# 7_seg_display.net
KiCad netlist of a schematic drawn in Altium Designer
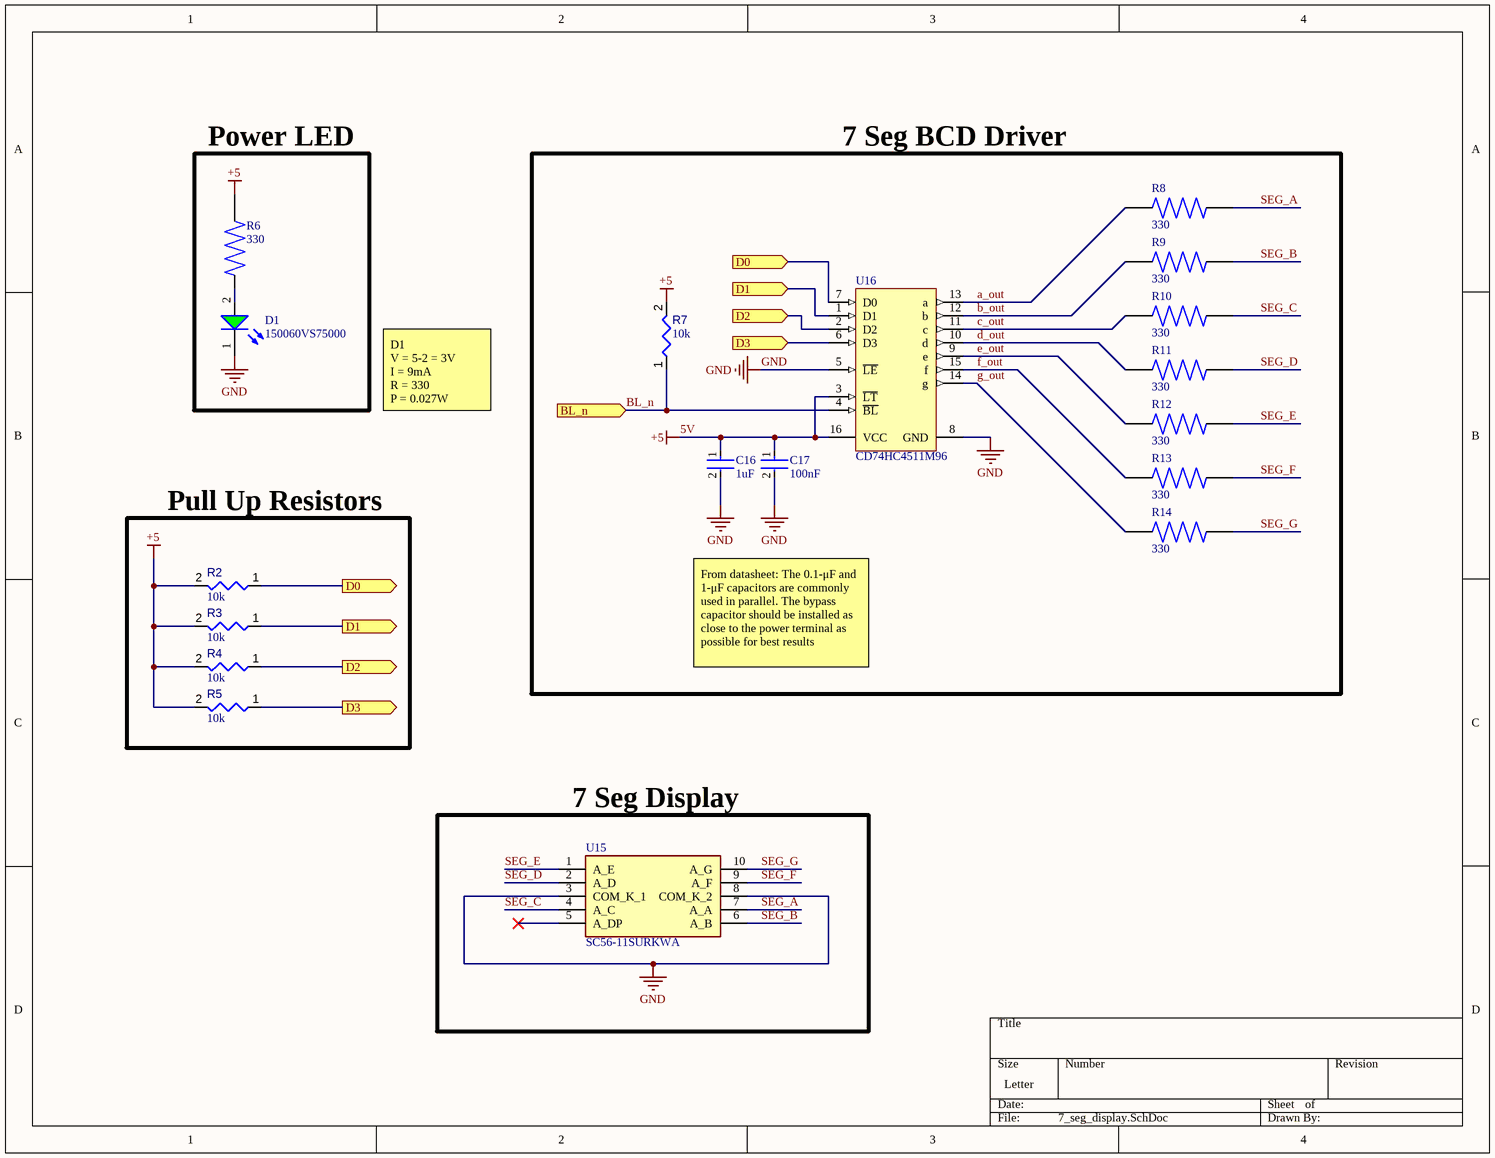
[diagram p0: 7_seg_display.SchDoc]

(export (version "E")
  (design (tool "Eeschema 10.0.6"))
  (components
    (comp (ref "C16")
      (value "1uF")
      (footprint "FP-CGA3E-0_3-0_1-IPC_A")
      (description "Cap Ceramic 1uF 16V X7R 10% Pad SMD 0603 +125°C Automotive T/R")
      (fields (field (name "TOLERANCE") "10%"))
      (libsource (lib "Altium Content Vault") (part "b4654b650e69147ec39a6b967a45e02"))
    )
    (comp (ref "C17")
      (value "100nF")
      (footprint "FP-CL10-IPC_A")
      (description "Cap Ceramic 100nF 16V X7R ±10% Pad SMD 0603 +125°C T/R")
      (fields (field (name "TOLERANCE") "10%"))
      (libsource (lib "Altium Content Vault") (part "b4654b650e69147ec39a6b967a45e02"))
    )
    (comp (ref "D1")
      (value "150060VS75000")
      (footprint "WL-SMCW_0603_150060xx75000")
      (description "WURTH ELEKTRONIK - 150060VS75000 - LED, Green, SMD, 0603, 30 mA, 2 V, 570 nm")
      (libsource (lib "Altium Content Vault") (part "LED_Green_2A-1K"))
    )
    (comp (ref "R2")
      (value "10k")
      (footprint "RESC1608X55X25ML10T15")
      (description "Chip Resistor, 10 KOhm, +/- 1%, 01 W, -55 to 155 degC, 0603 (1608 Metric)")
      (fields (field (name "POWER") "100mW") (field (name "TOLERANCE") "1%"))
      (libsource (lib "Lin Fu") (part "RES-2"))
    )
    (comp (ref "R3")
      (value "10k")
      (footprint "RESC1608X55X25ML10T15")
      (description "Chip Resistor, 10 KOhm, +/- 1%, 01 W, -55 to 155 degC, 0603 (1608 Metric)")
      (fields (field (name "POWER") "100mW") (field (name "TOLERANCE") "1%"))
      (libsource (lib "Lin Fu") (part "RES-2"))
    )
    (comp (ref "R4")
      (value "10k")
      (footprint "RESC1608X55X25ML10T15")
      (description "Chip Resistor, 10 KOhm, +/- 1%, 01 W, -55 to 155 degC, 0603 (1608 Metric)")
      (fields (field (name "POWER") "100mW") (field (name "TOLERANCE") "1%"))
      (libsource (lib "Lin Fu") (part "RES-2"))
    )
    (comp (ref "R5")
      (value "10k")
      (footprint "RESC1608X55X25ML10T15")
      (description "Chip Resistor, 10 KOhm, +/- 1%, 01 W, -55 to 155 degC, 0603 (1608 Metric)")
      (fields (field (name "POWER") "100mW") (field (name "TOLERANCE") "1%"))
      (libsource (lib "Lin Fu") (part "RES-2"))
    )
    (comp (ref "R6")
      (value "330")
      (footprint "RES_ERJ-PB3B3300V")
      (fields (field (name "MP") "ERJ-PB3B3300V") (field (name "MF") "Panasonic"))
      (libsource (lib "Lin Fu") (part "ERJ-PB3B3300V"))
    )
    (comp (ref "R7")
      (value "10k")
      (footprint "RESC1608X55X25ML10T15")
      (description "Chip Resistor, 10 KOhm, +/- 1%, 01 W, -55 to 155 degC, 0603 (1608 Metric)")
      (fields (field (name "POWER") "100mW") (field (name "TOLERANCE") "1%"))
      (libsource (lib "Lin Fu") (part "RES-2"))
    )
    (comp (ref "R8")
      (value "330")
      (footprint "RES_ERJ-PB3B3300V")
      (fields (field (name "MP") "ERJ-PB3B3300V") (field (name "MF") "Panasonic"))
      (libsource (lib "Lin Fu") (part "ERJ-PB3B3300V"))
    )
    (comp (ref "R9")
      (value "330")
      (footprint "RES_ERJ-PB3B3300V")
      (fields (field (name "MP") "ERJ-PB3B3300V") (field (name "MF") "Panasonic"))
      (libsource (lib "Lin Fu") (part "ERJ-PB3B3300V"))
    )
    (comp (ref "R10")
      (value "330")
      (footprint "RES_ERJ-PB3B3300V")
      (fields (field (name "MP") "ERJ-PB3B3300V") (field (name "MF") "Panasonic"))
      (libsource (lib "Lin Fu") (part "ERJ-PB3B3300V"))
    )
    (comp (ref "R11")
      (value "330")
      (footprint "RES_ERJ-PB3B3300V")
      (fields (field (name "MP") "ERJ-PB3B3300V") (field (name "MF") "Panasonic"))
      (libsource (lib "Lin Fu") (part "ERJ-PB3B3300V"))
    )
    (comp (ref "R12")
      (value "330")
      (footprint "RES_ERJ-PB3B3300V")
      (fields (field (name "MP") "ERJ-PB3B3300V") (field (name "MF") "Panasonic"))
      (libsource (lib "Lin Fu") (part "ERJ-PB3B3300V"))
    )
    (comp (ref "R13")
      (value "330")
      (footprint "RES_ERJ-PB3B3300V")
      (fields (field (name "MP") "ERJ-PB3B3300V") (field (name "MF") "Panasonic"))
      (libsource (lib "Lin Fu") (part "ERJ-PB3B3300V"))
    )
    (comp (ref "R14")
      (value "330")
      (footprint "RES_ERJ-PB3B3300V")
      (fields (field (name "MP") "ERJ-PB3B3300V") (field (name "MF") "Panasonic"))
      (libsource (lib "Lin Fu") (part "ERJ-PB3B3300V"))
    )
    (comp (ref "U15")
      (value "SC56-11SURKWA")
      (footprint "SamacSys:DIPS1524W75P254L1270H825Q10N")
      (description "Display")
      (fields (field (name "MOUSER PART NUMBER") "604-SC56-11SURKWA"))
      (libsource (lib "*") (part "SC56-11SURKWA"))
    )
    (comp (ref "U16")
      (value "CD74HC4511M96")
      (footprint "D0016A_N")
      (fields (field (name "MANUFACTURER") "Texas Instruments"))
      (libsource (lib "Altium Content Vault") (part "TI-CD54_74HCX4511-16"))
    )
  )
  (nets
    (net (code "1") (name "+5") (class "Default")
      (node (ref "C16") (pin "1") (pinfunction "1_1") (pintype "passive"))
      (node (ref "C17") (pin "1") (pinfunction "1_1") (pintype "passive"))
      (node (ref "R2") (pin "2") (pinfunction "2_2") (pintype "passive"))
      (node (ref "R3") (pin "2") (pinfunction "2_2") (pintype "passive"))
      (node (ref "R4") (pin "2") (pinfunction "2_2") (pintype "passive"))
      (node (ref "R5") (pin "2") (pinfunction "2_2") (pintype "passive"))
      (node (ref "R6") (pin "2") (pinfunction "2_2") (pintype "passive"))
      (node (ref "R7") (pin "2") (pinfunction "2_2") (pintype "passive"))
      (node (ref "U16") (pin "16") (pinfunction "VCC_16") (pintype "power_in"))
      (node (ref "U16") (pin "3") (pinfunction "~{LT}_3") (pintype "input"))
    )
    (net (code "2") (name "/BL_n") (class "Default")
      (node (ref "R7") (pin "1") (pinfunction "1_1") (pintype "passive"))
      (node (ref "U16") (pin "4") (pinfunction "~{BL}_4") (pintype "input"))
    )
    (net (code "3") (name "/D0") (class "Default")
      (node (ref "R2") (pin "1") (pinfunction "1_1") (pintype "passive"))
      (node (ref "U16") (pin "7") (pinfunction "D0_7") (pintype "input"))
    )
    (net (code "4") (name "/D1") (class "Default")
      (node (ref "R3") (pin "1") (pinfunction "1_1") (pintype "passive"))
      (node (ref "U16") (pin "1") (pinfunction "D1_1") (pintype "input"))
    )
    (net (code "5") (name "/D2") (class "Default")
      (node (ref "R4") (pin "1") (pinfunction "1_1") (pintype "passive"))
      (node (ref "U16") (pin "2") (pinfunction "D2_2") (pintype "input"))
    )
    (net (code "6") (name "/D3") (class "Default")
      (node (ref "R5") (pin "1") (pinfunction "1_1") (pintype "passive"))
      (node (ref "U16") (pin "6") (pinfunction "D3_6") (pintype "input"))
    )
    (net (code "7") (name "/SEG_A") (class "Default")
      (node (ref "R8") (pin "1") (pinfunction "1_1") (pintype "passive"))
      (node (ref "U15") (pin "7") (pinfunction "A_A_7") (pintype "passive"))
    )
    (net (code "8") (name "/SEG_B") (class "Default")
      (node (ref "R9") (pin "1") (pinfunction "1_1") (pintype "passive"))
      (node (ref "U15") (pin "6") (pinfunction "A_B_6") (pintype "passive"))
    )
    (net (code "9") (name "/SEG_C") (class "Default")
      (node (ref "R10") (pin "1") (pinfunction "1_1") (pintype "passive"))
      (node (ref "U15") (pin "4") (pinfunction "A_C_4") (pintype "passive"))
    )
    (net (code "10") (name "/SEG_D") (class "Default")
      (node (ref "R11") (pin "1") (pinfunction "1_1") (pintype "passive"))
      (node (ref "U15") (pin "2") (pinfunction "A_D_2") (pintype "passive"))
    )
    (net (code "11") (name "/SEG_E") (class "Default")
      (node (ref "R12") (pin "1") (pinfunction "1_1") (pintype "passive"))
      (node (ref "U15") (pin "1") (pinfunction "A_E_1") (pintype "passive"))
    )
    (net (code "12") (name "/SEG_F") (class "Default")
      (node (ref "R13") (pin "1") (pinfunction "1_1") (pintype "passive"))
      (node (ref "U15") (pin "9") (pinfunction "A_F_9") (pintype "passive"))
    )
    (net (code "13") (name "/SEG_G") (class "Default")
      (node (ref "R14") (pin "2") (pinfunction "2_2") (pintype "passive"))
      (node (ref "U15") (pin "10") (pinfunction "A_G_10") (pintype "passive"))
    )
    (net (code "14") (name "/a_out") (class "Default")
      (node (ref "R8") (pin "2") (pinfunction "2_2") (pintype "passive"))
      (node (ref "U16") (pin "13") (pinfunction "a_13") (pintype "output"))
    )
    (net (code "15") (name "/b_out") (class "Default")
      (node (ref "R9") (pin "2") (pinfunction "2_2") (pintype "passive"))
      (node (ref "U16") (pin "12") (pinfunction "b_12") (pintype "output"))
    )
    (net (code "16") (name "/c_out") (class "Default")
      (node (ref "R10") (pin "2") (pinfunction "2_2") (pintype "passive"))
      (node (ref "U16") (pin "11") (pinfunction "c_11") (pintype "output"))
    )
    (net (code "17") (name "/d_out") (class "Default")
      (node (ref "R11") (pin "2") (pinfunction "2_2") (pintype "passive"))
      (node (ref "U16") (pin "10") (pinfunction "d_10") (pintype "output"))
    )
    (net (code "18") (name "/e_out") (class "Default")
      (node (ref "R12") (pin "2") (pinfunction "2_2") (pintype "passive"))
      (node (ref "U16") (pin "9") (pinfunction "e_9") (pintype "output"))
    )
    (net (code "19") (name "/f_out") (class "Default")
      (node (ref "R13") (pin "2") (pinfunction "2_2") (pintype "passive"))
      (node (ref "U16") (pin "15") (pinfunction "f_15") (pintype "output"))
    )
    (net (code "20") (name "/g_out") (class "Default")
      (node (ref "R14") (pin "1") (pinfunction "1_1") (pintype "passive"))
      (node (ref "U16") (pin "14") (pinfunction "g_14") (pintype "output"))
    )
    (net (code "21") (name "GND") (class "Default")
      (node (ref "C16") (pin "2") (pinfunction "2_2") (pintype "passive"))
      (node (ref "C17") (pin "2") (pinfunction "2_2") (pintype "passive"))
      (node (ref "D1") (pin "1") (pinfunction "K_1") (pintype "passive"))
      (node (ref "U15") (pin "3") (pinfunction "COM_K_1_3") (pintype "passive"))
      (node (ref "U15") (pin "8") (pinfunction "COM_K_2_8") (pintype "passive"))
      (node (ref "U16") (pin "5") (pinfunction "~{LE}_5") (pintype "input"))
      (node (ref "U16") (pin "8") (pinfunction "GND_8") (pintype "power_in"))
    )
    (net (code "22") (name "Net-(D1-A)") (class "Default")
      (node (ref "D1") (pin "2") (pinfunction "A_2") (pintype "passive"))
      (node (ref "R6") (pin "1") (pinfunction "1_1") (pintype "passive"))
    )
    (net (code "23") (name "unconnected-(U15-A_DP-Pad5)") (class "Default")
      (node (ref "U15") (pin "5") (pinfunction "A_DP_5") (pintype "passive+no_connect"))
    )
  )
)
